# G502.net
KiCad netlist of a schematic drawn in EAGLE
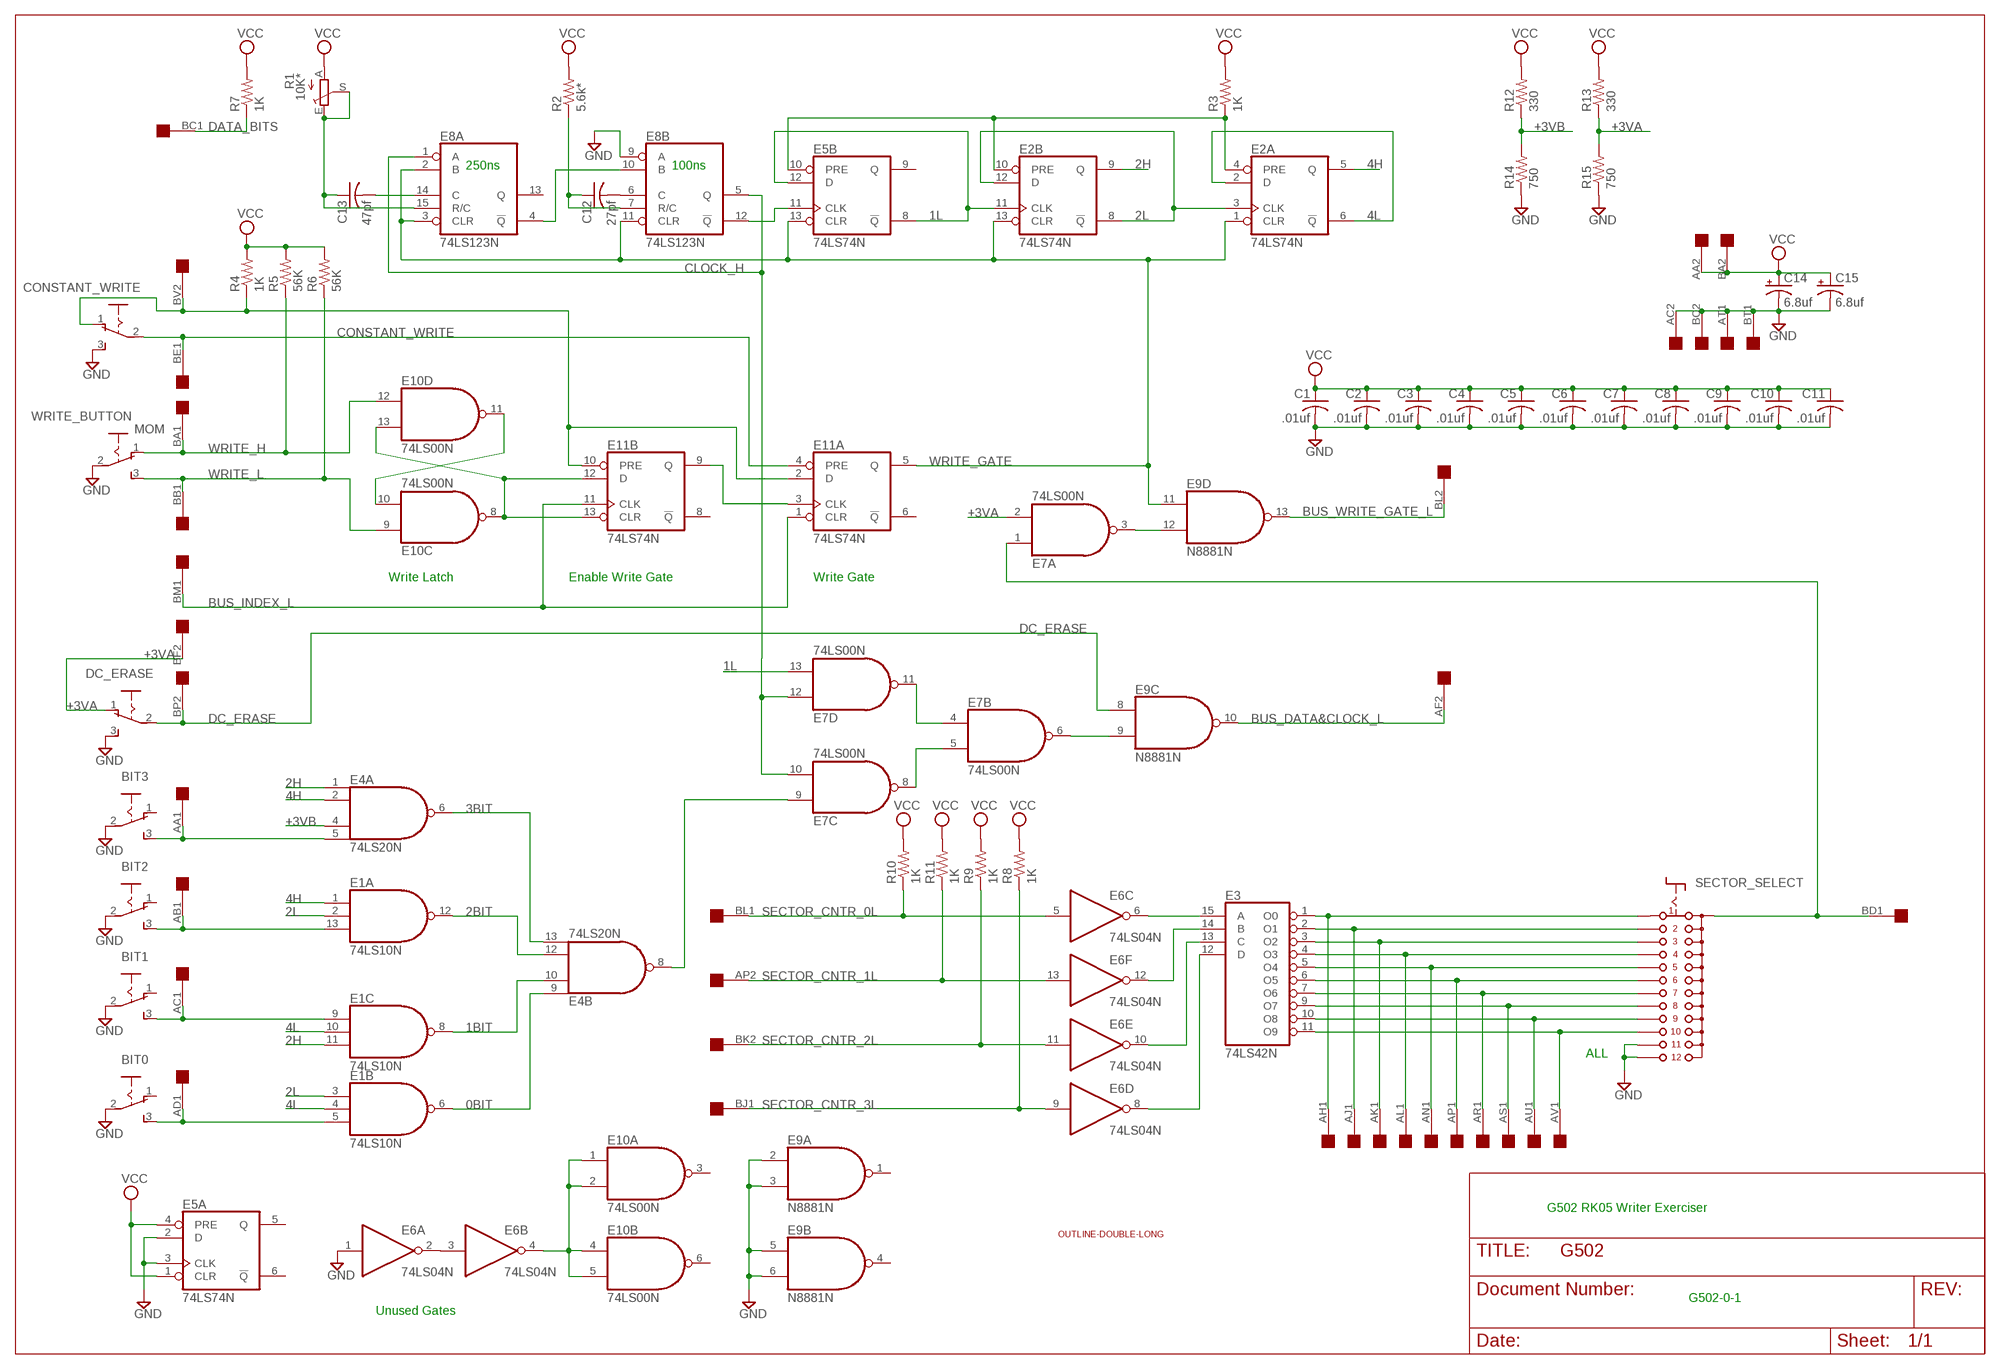
[diagram p0: schematic, sheet 1]

(export (version "E")
  (design (tool "Eeschema 10.0.6"))
  (components
    (comp (ref "AB04")
      (value "DOUBLE")
      (footprint "eagle-import:EDGE-CON4")
      (libsource (lib "eagle-import") (part "DOUBLE"))
    )
    (comp (ref "BIT0")
      (value "255SB")
      (footprint "eagle-import:255SB")
      (libsource (lib "eagle-import") (part "255SB"))
    )
    (comp (ref "BIT1")
      (value "255SB")
      (footprint "eagle-import:255SB")
      (libsource (lib "eagle-import") (part "255SB"))
    )
    (comp (ref "BIT2")
      (value "255SB")
      (footprint "eagle-import:255SB")
      (libsource (lib "eagle-import") (part "255SB"))
    )
    (comp (ref "BIT3")
      (value "255SB")
      (footprint "eagle-import:255SB")
      (libsource (lib "eagle-import") (part "255SB"))
    )
    (comp (ref "C1")
      (value ".01uf")
      (footprint "eagle-import:C075-032X103")
      (libsource (lib "eagle-import") (part "C-US075-032X103"))
    )
    (comp (ref "C2")
      (value ".01uf")
      (footprint "eagle-import:C075-032X103")
      (libsource (lib "eagle-import") (part "C-US075-032X103"))
    )
    (comp (ref "C3")
      (value ".01uf")
      (footprint "eagle-import:C075-032X103")
      (libsource (lib "eagle-import") (part "C-US075-032X103"))
    )
    (comp (ref "C4")
      (value ".01uf")
      (footprint "eagle-import:C075-032X103")
      (libsource (lib "eagle-import") (part "C-US075-032X103"))
    )
    (comp (ref "C5")
      (value ".01uf")
      (footprint "eagle-import:C075-032X103")
      (libsource (lib "eagle-import") (part "C-US075-032X103"))
    )
    (comp (ref "C6")
      (value ".01uf")
      (footprint "eagle-import:C075-032X103")
      (libsource (lib "eagle-import") (part "C-US075-032X103"))
    )
    (comp (ref "C7")
      (value ".01uf")
      (footprint "eagle-import:C075-032X103")
      (libsource (lib "eagle-import") (part "C-US075-032X103"))
    )
    (comp (ref "C8")
      (value ".01uf")
      (footprint "eagle-import:C075-032X103")
      (libsource (lib "eagle-import") (part "C-US075-032X103"))
    )
    (comp (ref "C9")
      (value ".01uf")
      (footprint "eagle-import:C075-032X103")
      (libsource (lib "eagle-import") (part "C-US075-032X103"))
    )
    (comp (ref "C10")
      (value ".01uf")
      (footprint "eagle-import:C075-032X103")
      (libsource (lib "eagle-import") (part "C-US075-032X103"))
    )
    (comp (ref "C11")
      (value ".01uf")
      (footprint "eagle-import:C075-032X103")
      (libsource (lib "eagle-import") (part "C-US075-032X103"))
    )
    (comp (ref "C12")
      (value "27pf")
      (footprint "eagle-import:C075-032X103")
      (libsource (lib "eagle-import") (part "C-US075-032X103"))
    )
    (comp (ref "C13")
      (value "47pf")
      (footprint "eagle-import:C075-032X103")
      (libsource (lib "eagle-import") (part "C-US075-032X103"))
    )
    (comp (ref "C14")
      (value "6.8uf")
      (footprint "eagle-import:E25-9")
      (libsource (lib "eagle-import") (part "CPOL-USE25-9AXIAL"))
    )
    (comp (ref "C15")
      (value "6.8uf")
      (footprint "eagle-import:E25-9")
      (libsource (lib "eagle-import") (part "CPOL-USE25-9AXIAL"))
    )
    (comp (ref "CONSTANT_WRITE")
      (value "255SB")
      (footprint "eagle-import:255SB")
      (libsource (lib "eagle-import") (part "255SB"))
    )
    (comp (ref "DC_ERASE")
      (value "255SB")
      (footprint "eagle-import:255SB")
      (libsource (lib "eagle-import") (part "255SB"))
    )
    (comp (ref "E1")
      (value "74LS10N")
      (footprint "eagle-import:DIL14")
      (libsource (lib "eagle-import") (part "7410NLS"))
    )
    (comp (ref "E2")
      (value "74LS74N")
      (footprint "eagle-import:DIL14")
      (libsource (lib "eagle-import") (part "7474NLS"))
    )
    (comp (ref "E3")
      (value "74LS42N")
      (footprint "eagle-import:DIL16")
      (libsource (lib "eagle-import") (part "7442NLS"))
    )
    (comp (ref "E4")
      (value "74LS20N")
      (footprint "eagle-import:DIL14")
      (libsource (lib "eagle-import") (part "7420NLS"))
    )
    (comp (ref "E5")
      (value "74LS74N")
      (footprint "eagle-import:DIL14")
      (libsource (lib "eagle-import") (part "7474NLS"))
    )
    (comp (ref "E6")
      (value "74LS04N")
      (footprint "eagle-import:DIL14")
      (libsource (lib "eagle-import") (part "7404NLS"))
    )
    (comp (ref "E7")
      (value "74LS00N")
      (footprint "eagle-import:DIL14")
      (libsource (lib "eagle-import") (part "7400NLS"))
    )
    (comp (ref "E8")
      (value "74LS123N")
      (footprint "eagle-import:DIL16")
      (libsource (lib "eagle-import") (part "74123NLS"))
    )
    (comp (ref "E9")
      (value "N8881N")
      (footprint "eagle-import:DIL14")
      (libsource (lib "eagle-import") (part "N8881N"))
    )
    (comp (ref "E10")
      (value "74LS00N")
      (footprint "eagle-import:DIL14")
      (libsource (lib "eagle-import") (part "7400NLS"))
    )
    (comp (ref "E11")
      (value "74LS74N")
      (footprint "eagle-import:DIL14")
      (libsource (lib "eagle-import") (part "7474NLS"))
    )
    (comp (ref "R1")
      (value "10K*")
      (footprint "eagle-import:SP19L")
      (libsource (lib "eagle-import") (part "TRIM_EU-B90P"))
    )
    (comp (ref "R2")
      (value "5.6k*")
      (footprint "eagle-import:0207_10")
      (libsource (lib "eagle-import") (part "R-US_0207/10"))
    )
    (comp (ref "R3")
      (value "1K")
      (footprint "eagle-import:0207_10")
      (libsource (lib "eagle-import") (part "R-US_0207/10"))
    )
    (comp (ref "R4")
      (value "1K")
      (footprint "eagle-import:0207_10")
      (libsource (lib "eagle-import") (part "R-US_0207/10"))
    )
    (comp (ref "R5")
      (value "56K")
      (footprint "eagle-import:0207_10")
      (libsource (lib "eagle-import") (part "R-US_0207/10"))
    )
    (comp (ref "R6")
      (value "56K")
      (footprint "eagle-import:0207_10")
      (libsource (lib "eagle-import") (part "R-US_0207/10"))
    )
    (comp (ref "R7")
      (value "1K")
      (footprint "eagle-import:0207_10")
      (libsource (lib "eagle-import") (part "R-US_0207/10"))
    )
    (comp (ref "R8")
      (value "1K")
      (footprint "eagle-import:0207_10")
      (libsource (lib "eagle-import") (part "R-US_0207/10"))
    )
    (comp (ref "R9")
      (value "1K")
      (footprint "eagle-import:0207_10")
      (libsource (lib "eagle-import") (part "R-US_0207/10"))
    )
    (comp (ref "R10")
      (value "1K")
      (footprint "eagle-import:0207_10")
      (libsource (lib "eagle-import") (part "R-US_0207/10"))
    )
    (comp (ref "R11")
      (value "1K")
      (footprint "eagle-import:0207_10")
      (libsource (lib "eagle-import") (part "R-US_0207/10"))
    )
    (comp (ref "R12")
      (value "330")
      (footprint "eagle-import:0207_10")
      (libsource (lib "eagle-import") (part "R-US_0207/10"))
    )
    (comp (ref "R13")
      (value "330")
      (footprint "eagle-import:0207_10")
      (libsource (lib "eagle-import") (part "R-US_0207/10"))
    )
    (comp (ref "R14")
      (value "750")
      (footprint "eagle-import:0207_10")
      (libsource (lib "eagle-import") (part "R-US_0207/10"))
    )
    (comp (ref "R15")
      (value "750")
      (footprint "eagle-import:0207_10")
      (libsource (lib "eagle-import") (part "R-US_0207/10"))
    )
    (comp (ref "SECTOR_SELECT")
      (value "CK101X12")
      (footprint "eagle-import:CK101X12")
      (libsource (lib "eagle-import") (part "CK101X12"))
    )
    (comp (ref "U$2")
      (value "OUTLINE-DOUBLE-LONG")
      (footprint "eagle-import:DOUBLE-LONG")
      (libsource (lib "eagle-import") (part "OUTLINE-DOUBLE-LONG"))
    )
    (comp (ref "WRITE_BUTTON")
      (value "MOM")
      (footprint "eagle-import:255SB")
      (libsource (lib "eagle-import") (part "255SB"))
    )
  )
  (nets
    (net (code "1") (name "/+3VA") (class "Default")
      (node (ref "AB04") (pin "BF2") (pinfunction "1_BF2") (pintype "bidirectional"))
      (node (ref "DC_ERASE") (pin "1") (pinfunction "O_1") (pintype "passive"))
      (node (ref "E7") (pin "2") (pinfunction "I1_2") (pintype "input"))
      (node (ref "R13") (pin "1") (pinfunction "1_1") (pintype "passive"))
      (node (ref "R15") (pin "2") (pinfunction "2_2") (pintype "passive"))
    )
    (net (code "2") (name "/+3VB") (class "Default")
      (node (ref "E4") (pin "4") (pinfunction "I2_4") (pintype "input"))
      (node (ref "R12") (pin "1") (pinfunction "1_1") (pintype "passive"))
      (node (ref "R14") (pin "2") (pinfunction "2_2") (pintype "passive"))
    )
    (net (code "3") (name "/0BIT") (class "Default")
      (node (ref "E1") (pin "6") (pinfunction "O_6") (pintype "output"))
      (node (ref "E4") (pin "9") (pinfunction "I0_9") (pintype "input"))
    )
    (net (code "4") (name "/1BIT") (class "Default")
      (node (ref "E1") (pin "8") (pinfunction "O_8") (pintype "output"))
      (node (ref "E4") (pin "10") (pinfunction "I1_10") (pintype "input"))
    )
    (net (code "5") (name "/1L") (class "Default")
      (node (ref "E2") (pin "11") (pinfunction "CLK_11") (pintype "input"))
      (node (ref "E5") (pin "12") (pinfunction "D_12") (pintype "input"))
      (node (ref "E5") (pin "8") (pinfunction "~{Q}_8") (pintype "output"))
      (node (ref "E7") (pin "13") (pinfunction "I1_13") (pintype "input"))
    )
    (net (code "6") (name "/2BIT") (class "Default")
      (node (ref "E1") (pin "12") (pinfunction "O_12") (pintype "output"))
      (node (ref "E4") (pin "12") (pinfunction "I2_12") (pintype "input"))
    )
    (net (code "7") (name "/2H") (class "Default")
      (node (ref "E1") (pin "11") (pinfunction "I2_11") (pintype "input"))
      (node (ref "E2") (pin "9") (pinfunction "Q_9") (pintype "output"))
      (node (ref "E4") (pin "1") (pinfunction "I0_1") (pintype "input"))
    )
    (net (code "8") (name "/2L") (class "Default")
      (node (ref "E1") (pin "2") (pinfunction "I1_2") (pintype "input"))
      (node (ref "E1") (pin "3") (pinfunction "I0_3") (pintype "input"))
      (node (ref "E2") (pin "12") (pinfunction "D_12") (pintype "input"))
      (node (ref "E2") (pin "3") (pinfunction "CLK_3") (pintype "input"))
      (node (ref "E2") (pin "8") (pinfunction "~{Q}_8") (pintype "output"))
    )
    (net (code "9") (name "/3BIT") (class "Default")
      (node (ref "E4") (pin "13") (pinfunction "I3_13") (pintype "input"))
      (node (ref "E4") (pin "6") (pinfunction "O_6") (pintype "output"))
    )
    (net (code "10") (name "/4H") (class "Default")
      (node (ref "E1") (pin "1") (pinfunction "I0_1") (pintype "input"))
      (node (ref "E2") (pin "5") (pinfunction "Q_5") (pintype "output"))
      (node (ref "E4") (pin "2") (pinfunction "I1_2") (pintype "input"))
    )
    (net (code "11") (name "/4L") (class "Default")
      (node (ref "E1") (pin "10") (pinfunction "I1_10") (pintype "input"))
      (node (ref "E1") (pin "4") (pinfunction "I1_4") (pintype "input"))
      (node (ref "E2") (pin "2") (pinfunction "D_2") (pintype "input"))
      (node (ref "E2") (pin "6") (pinfunction "~{Q}_6") (pintype "output"))
    )
    (net (code "12") (name "/BUS_DATA&CLOCK_L") (class "Default")
      (node (ref "AB04") (pin "AF2") (pinfunction "1_AF2") (pintype "bidirectional"))
      (node (ref "E9") (pin "10") (pinfunction "O_10") (pintype "open_collector"))
    )
    (net (code "13") (name "/BUS_INDEX_L") (class "Default")
      (node (ref "AB04") (pin "BM1") (pinfunction "1_BM1") (pintype "bidirectional"))
      (node (ref "E11") (pin "1") (pinfunction "CLR_1") (pintype "input"))
      (node (ref "E11") (pin "11") (pinfunction "CLK_11") (pintype "input"))
    )
    (net (code "14") (name "/BUS_WRITE_GATE_L") (class "Default")
      (node (ref "AB04") (pin "BL2") (pinfunction "1_BL2") (pintype "bidirectional"))
      (node (ref "E9") (pin "13") (pinfunction "O_13") (pintype "open_collector"))
    )
    (net (code "15") (name "/CLOCK_H") (class "Default")
      (node (ref "E7") (pin "10") (pinfunction "I1_10") (pintype "input"))
      (node (ref "E7") (pin "12") (pinfunction "I0_12") (pintype "input"))
      (node (ref "E8") (pin "1") (pinfunction "A_1") (pintype "input"))
      (node (ref "E8") (pin "5") (pinfunction "Q_5") (pintype "output"))
    )
    (net (code "16") (name "/CONSTANT_WRITE") (class "Default")
      (node (ref "AB04") (pin "BE1") (pinfunction "1_BE1") (pintype "bidirectional"))
      (node (ref "CONSTANT_WRITE") (pin "2") (pinfunction "P_2") (pintype "passive"))
      (node (ref "E11") (pin "4") (pinfunction "PRE_4") (pintype "input"))
    )
    (net (code "17") (name "/DATA_BITS") (class "Default")
      (node (ref "AB04") (pin "BC1") (pinfunction "1_BC1") (pintype "bidirectional"))
      (node (ref "R7") (pin "1") (pinfunction "1_1") (pintype "passive"))
    )
    (net (code "18") (name "/DC_ERASE") (class "Default")
      (node (ref "AB04") (pin "BP2") (pinfunction "1_BP2") (pintype "bidirectional"))
      (node (ref "DC_ERASE") (pin "2") (pinfunction "P_2") (pintype "passive"))
      (node (ref "E9") (pin "8") (pinfunction "I0_8") (pintype "input"))
    )
    (net (code "19") (name "/SECTOR_CNTR_0L") (class "Default")
      (node (ref "AB04") (pin "BL1") (pinfunction "1_BL1") (pintype "bidirectional"))
      (node (ref "E6") (pin "5") (pinfunction "I_5") (pintype "input"))
      (node (ref "R10") (pin "1") (pinfunction "1_1") (pintype "passive"))
    )
    (net (code "20") (name "/SECTOR_CNTR_1L") (class "Default")
      (node (ref "AB04") (pin "AP2") (pinfunction "1_AP2") (pintype "bidirectional"))
      (node (ref "E6") (pin "13") (pinfunction "I_13") (pintype "input"))
      (node (ref "R11") (pin "1") (pinfunction "1_1") (pintype "passive"))
    )
    (net (code "21") (name "/SECTOR_CNTR_2L") (class "Default")
      (node (ref "AB04") (pin "BK2") (pinfunction "1_BK2") (pintype "bidirectional"))
      (node (ref "E6") (pin "11") (pinfunction "I_11") (pintype "input"))
      (node (ref "R9") (pin "1") (pinfunction "1_1") (pintype "passive"))
    )
    (net (code "22") (name "/SECTOR_CNTR_3L") (class "Default")
      (node (ref "AB04") (pin "BJ1") (pinfunction "1_BJ1") (pintype "bidirectional"))
      (node (ref "E6") (pin "9") (pinfunction "I_9") (pintype "input"))
      (node (ref "R8") (pin "1") (pinfunction "1_1") (pintype "passive"))
    )
    (net (code "23") (name "/WRITE_GATE") (class "Default")
      (node (ref "E11") (pin "5") (pinfunction "Q_5") (pintype "output"))
      (node (ref "E2") (pin "1") (pinfunction "CLR_1") (pintype "input"))
      (node (ref "E2") (pin "13") (pinfunction "CLR_13") (pintype "input"))
      (node (ref "E5") (pin "13") (pinfunction "CLR_13") (pintype "input"))
      (node (ref "E8") (pin "11") (pinfunction "CLR_11") (pintype "input"))
      (node (ref "E8") (pin "2") (pinfunction "B_2") (pintype "input"))
      (node (ref "E8") (pin "3") (pinfunction "CLR_3") (pintype "input"))
      (node (ref "E9") (pin "11") (pinfunction "I0_11") (pintype "input"))
    )
    (net (code "24") (name "/WRITE_H") (class "Default")
      (node (ref "AB04") (pin "BA1") (pinfunction "1_BA1") (pintype "bidirectional"))
      (node (ref "E10") (pin "12") (pinfunction "I0_12") (pintype "input"))
      (node (ref "R5") (pin "1") (pinfunction "1_1") (pintype "passive"))
      (node (ref "WRITE_BUTTON") (pin "1") (pinfunction "O_1") (pintype "passive"))
    )
    (net (code "25") (name "/WRITE_L") (class "Default")
      (node (ref "AB04") (pin "BB1") (pinfunction "1_BB1") (pintype "bidirectional"))
      (node (ref "E10") (pin "9") (pinfunction "I0_9") (pintype "input"))
      (node (ref "R6") (pin "1") (pinfunction "1_1") (pintype "passive"))
      (node (ref "WRITE_BUTTON") (pin "3") (pinfunction "S_3") (pintype "passive"))
    )
    (net (code "26") (name "GND") (class "Default")
      (node (ref "AB04") (pin "AC2") (pinfunction "1_AC2") (pintype "bidirectional"))
      (node (ref "AB04") (pin "AT1") (pinfunction "1_AT1") (pintype "bidirectional"))
      (node (ref "AB04") (pin "BC2") (pinfunction "1_BC2") (pintype "bidirectional"))
      (node (ref "AB04") (pin "BT1") (pinfunction "1_BT1") (pintype "bidirectional"))
      (node (ref "BIT0") (pin "2") (pinfunction "P_2") (pintype "passive"))
      (node (ref "BIT1") (pin "2") (pinfunction "P_2") (pintype "passive"))
      (node (ref "BIT2") (pin "2") (pinfunction "P_2") (pintype "passive"))
      (node (ref "BIT3") (pin "2") (pinfunction "P_2") (pintype "passive"))
      (node (ref "C1") (pin "2") (pinfunction "2_2") (pintype "passive"))
      (node (ref "C10") (pin "2") (pinfunction "2_2") (pintype "passive"))
      (node (ref "C11") (pin "2") (pinfunction "2_2") (pintype "passive"))
      (node (ref "C14") (pin "-") (pinfunction "-_-") (pintype "passive"))
      (node (ref "C15") (pin "-") (pinfunction "-_-") (pintype "passive"))
      (node (ref "C2") (pin "2") (pinfunction "2_2") (pintype "passive"))
      (node (ref "C3") (pin "2") (pinfunction "2_2") (pintype "passive"))
      (node (ref "C4") (pin "2") (pinfunction "2_2") (pintype "passive"))
      (node (ref "C5") (pin "2") (pinfunction "2_2") (pintype "passive"))
      (node (ref "C6") (pin "2") (pinfunction "2_2") (pintype "passive"))
      (node (ref "C7") (pin "2") (pinfunction "2_2") (pintype "passive"))
      (node (ref "C8") (pin "2") (pinfunction "2_2") (pintype "passive"))
      (node (ref "C9") (pin "2") (pinfunction "2_2") (pintype "passive"))
      (node (ref "CONSTANT_WRITE") (pin "3") (pinfunction "S_3") (pintype "passive"))
      (node (ref "DC_ERASE") (pin "3") (pinfunction "S_3") (pintype "passive"))
      (node (ref "E5") (pin "2") (pinfunction "D_2") (pintype "input"))
      (node (ref "E5") (pin "3") (pinfunction "CLK_3") (pintype "input"))
      (node (ref "E6") (pin "1") (pinfunction "I_1") (pintype "input"))
      (node (ref "E8") (pin "9") (pinfunction "A_9") (pintype "input"))
      (node (ref "E9") (pin "2") (pinfunction "I0_2") (pintype "input"))
      (node (ref "E9") (pin "3") (pinfunction "I1_3") (pintype "input"))
      (node (ref "E9") (pin "5") (pinfunction "I0_5") (pintype "input"))
      (node (ref "E9") (pin "6") (pinfunction "I1_6") (pintype "input"))
      (node (ref "R14") (pin "1") (pinfunction "1_1") (pintype "passive"))
      (node (ref "R15") (pin "1") (pinfunction "1_1") (pintype "passive"))
      (node (ref "SECTOR_SELECT") (pin "11") (pinfunction "11_11") (pintype "passive"))
      (node (ref "SECTOR_SELECT") (pin "12") (pinfunction "12_12") (pintype "passive"))
      (node (ref "WRITE_BUTTON") (pin "2") (pinfunction "P_2") (pintype "passive"))
    )
    (net (code "27") (name "Net-(AB04A-1)") (class "Default")
      (node (ref "AB04") (pin "AA1") (pinfunction "1_AA1") (pintype "bidirectional"))
      (node (ref "BIT3") (pin "3") (pinfunction "S_3") (pintype "passive"))
      (node (ref "E4") (pin "5") (pinfunction "I3_5") (pintype "input"))
    )
    (net (code "28") (name "Net-(AB04AA-1)") (class "Default")
      (node (ref "AB04") (pin "AR1") (pinfunction "1_AR1") (pintype "bidirectional"))
      (node (ref "E3") (pin "7") (pinfunction "O6_7") (pintype "output"))
      (node (ref "SECTOR_SELECT") (pin "7") (pinfunction "7_7") (pintype "passive"))
    )
    (net (code "29") (name "Net-(AB04AC-1)") (class "Default")
      (node (ref "AB04") (pin "AS1") (pinfunction "1_AS1") (pintype "bidirectional"))
      (node (ref "E3") (pin "9") (pinfunction "O7_9") (pintype "output"))
      (node (ref "SECTOR_SELECT") (pin "8") (pinfunction "8_8") (pintype "passive"))
    )
    (net (code "30") (name "Net-(AB04AG-1)") (class "Default")
      (node (ref "AB04") (pin "AU1") (pinfunction "1_AU1") (pintype "bidirectional"))
      (node (ref "E3") (pin "10") (pinfunction "O8_10") (pintype "output"))
      (node (ref "SECTOR_SELECT") (pin "9") (pinfunction "9_9") (pintype "passive"))
    )
    (net (code "31") (name "Net-(AB04AI-1)") (class "Default")
      (node (ref "AB04") (pin "AV1") (pinfunction "1_AV1") (pintype "bidirectional"))
      (node (ref "E3") (pin "11") (pinfunction "O9_11") (pintype "output"))
      (node (ref "SECTOR_SELECT") (pin "10") (pinfunction "10_10") (pintype "passive"))
    )
    (net (code "32") (name "Net-(AB04AQ-1)") (class "Default")
      (node (ref "AB04") (pin "BD1") (pinfunction "1_BD1") (pintype "bidirectional"))
      (node (ref "E7") (pin "1") (pinfunction "I0_1") (pintype "input"))
      (node (ref "SECTOR_SELECT") (pin "A") (pinfunction "A_A") (pintype "passive"))
    )
    (net (code "33") (name "Net-(AB04BT-1)") (class "Default")
      (node (ref "AB04") (pin "BV2") (pinfunction "1_BV2") (pintype "bidirectional"))
      (node (ref "CONSTANT_WRITE") (pin "1") (pinfunction "O_1") (pintype "passive"))
      (node (ref "E11") (pin "10") (pinfunction "PRE_10") (pintype "input"))
      (node (ref "E11") (pin "2") (pinfunction "D_2") (pintype "input"))
      (node (ref "R4") (pin "1") (pinfunction "1_1") (pintype "passive"))
    )
    (net (code "34") (name "Net-(AB04C-1)") (class "Default")
      (node (ref "AB04") (pin "AB1") (pinfunction "1_AB1") (pintype "bidirectional"))
      (node (ref "BIT2") (pin "3") (pinfunction "S_3") (pintype "passive"))
      (node (ref "E1") (pin "13") (pinfunction "I2_13") (pintype "input"))
    )
    (net (code "35") (name "Net-(AB04E-1)") (class "Default")
      (node (ref "AB04") (pin "AC1") (pinfunction "1_AC1") (pintype "bidirectional"))
      (node (ref "BIT1") (pin "3") (pinfunction "S_3") (pintype "passive"))
      (node (ref "E1") (pin "9") (pinfunction "I0_9") (pintype "input"))
    )
    (net (code "36") (name "Net-(AB04G-1)") (class "Default")
      (node (ref "AB04") (pin "AD1") (pinfunction "1_AD1") (pintype "bidirectional"))
      (node (ref "BIT0") (pin "3") (pinfunction "S_3") (pintype "passive"))
      (node (ref "E1") (pin "5") (pinfunction "I2_5") (pintype "input"))
    )
    (net (code "37") (name "Net-(AB04M-1)") (class "Default")
      (node (ref "AB04") (pin "AH1") (pinfunction "1_AH1") (pintype "bidirectional"))
      (node (ref "E3") (pin "1") (pinfunction "O0_1") (pintype "output"))
      (node (ref "SECTOR_SELECT") (pin "1") (pinfunction "1_1") (pintype "passive"))
    )
    (net (code "38") (name "Net-(AB04O-1)") (class "Default")
      (node (ref "AB04") (pin "AJ1") (pinfunction "1_AJ1") (pintype "bidirectional"))
      (node (ref "E3") (pin "2") (pinfunction "O1_2") (pintype "output"))
      (node (ref "SECTOR_SELECT") (pin "2") (pinfunction "2_2") (pintype "passive"))
    )
    (net (code "39") (name "Net-(AB04Q-1)") (class "Default")
      (node (ref "AB04") (pin "AK1") (pinfunction "1_AK1") (pintype "bidirectional"))
      (node (ref "E3") (pin "3") (pinfunction "O2_3") (pintype "output"))
      (node (ref "SECTOR_SELECT") (pin "3") (pinfunction "3_3") (pintype "passive"))
    )
    (net (code "40") (name "Net-(AB04S-1)") (class "Default")
      (node (ref "AB04") (pin "AL1") (pinfunction "1_AL1") (pintype "bidirectional"))
      (node (ref "E3") (pin "4") (pinfunction "O3_4") (pintype "output"))
      (node (ref "SECTOR_SELECT") (pin "4") (pinfunction "4_4") (pintype "passive"))
    )
    (net (code "41") (name "Net-(AB04W-1)") (class "Default")
      (node (ref "AB04") (pin "AN1") (pinfunction "1_AN1") (pintype "bidirectional"))
      (node (ref "E3") (pin "5") (pinfunction "O4_5") (pintype "output"))
      (node (ref "SECTOR_SELECT") (pin "5") (pinfunction "5_5") (pintype "passive"))
    )
    (net (code "42") (name "Net-(AB04Y-1)") (class "Default")
      (node (ref "AB04") (pin "AP1") (pinfunction "1_AP1") (pintype "bidirectional"))
      (node (ref "E3") (pin "6") (pinfunction "O5_6") (pintype "output"))
      (node (ref "SECTOR_SELECT") (pin "6") (pinfunction "6_6") (pintype "passive"))
    )
    (net (code "43") (name "Net-(E2A-PRE)") (class "Default")
      (node (ref "E2") (pin "10") (pinfunction "PRE_10") (pintype "input"))
      (node (ref "E2") (pin "4") (pinfunction "PRE_4") (pintype "input"))
      (node (ref "E5") (pin "10") (pinfunction "PRE_10") (pintype "input"))
      (node (ref "R3") (pin "1") (pinfunction "1_1") (pintype "passive"))
    )
    (net (code "44") (name "Net-(E3A-A)") (class "Default")
      (node (ref "E3") (pin "15") (pinfunction "A_15") (pintype "input"))
      (node (ref "E6") (pin "6") (pinfunction "O_6") (pintype "output"))
    )
    (net (code "45") (name "Net-(E3A-B)") (class "Default")
      (node (ref "E3") (pin "14") (pinfunction "B_14") (pintype "input"))
      (node (ref "E6") (pin "12") (pinfunction "O_12") (pintype "output"))
    )
    (net (code "46") (name "Net-(E3A-C)") (class "Default")
      (node (ref "E3") (pin "13") (pinfunction "C_13") (pintype "input"))
      (node (ref "E6") (pin "10") (pinfunction "O_10") (pintype "output"))
    )
    (net (code "47") (name "Net-(E3A-D)") (class "Default")
      (node (ref "E3") (pin "12") (pinfunction "D_12") (pintype "input"))
      (node (ref "E6") (pin "8") (pinfunction "O_8") (pintype "output"))
    )
    (net (code "48") (name "Net-(E4B-O)") (class "Default")
      (node (ref "E4") (pin "8") (pinfunction "O_8") (pintype "output"))
      (node (ref "E7") (pin "9") (pinfunction "I0_9") (pintype "input"))
    )
    (net (code "49") (name "Net-(E5B-CLK)") (class "Default")
      (node (ref "E5") (pin "11") (pinfunction "CLK_11") (pintype "input"))
      (node (ref "E8") (pin "12") (pinfunction "~{Q}_12") (pintype "output"))
    )
    (net (code "50") (name "Net-(E6A-O)") (class "Default")
      (node (ref "E6") (pin "2") (pinfunction "O_2") (pintype "output"))
      (node (ref "E6") (pin "3") (pinfunction "I_3") (pintype "input"))
    )
    (net (code "51") (name "Net-(E7A-O)") (class "Default")
      (node (ref "E7") (pin "3") (pinfunction "O_3") (pintype "output"))
      (node (ref "E9") (pin "12") (pinfunction "I1_12") (pintype "input"))
    )
    (net (code "52") (name "Net-(E7B-I0)") (class "Default")
      (node (ref "E7") (pin "11") (pinfunction "O_11") (pintype "output"))
      (node (ref "E7") (pin "4") (pinfunction "I0_4") (pintype "input"))
    )
    (net (code "53") (name "Net-(E7B-I1)") (class "Default")
      (node (ref "E7") (pin "5") (pinfunction "I1_5") (pintype "input"))
      (node (ref "E7") (pin "8") (pinfunction "O_8") (pintype "output"))
    )
    (net (code "54") (name "Net-(E7B-O)") (class "Default")
      (node (ref "E7") (pin "6") (pinfunction "O_6") (pintype "output"))
      (node (ref "E9") (pin "9") (pinfunction "I1_9") (pintype "input"))
    )
    (net (code "55") (name "Net-(E8A-C)") (class "Default")
      (node (ref "C13") (pin "2") (pinfunction "2_2") (pintype "passive"))
      (node (ref "E8") (pin "14") (pinfunction "C_14") (pintype "input"))
    )
    (net (code "56") (name "Net-(E8A-R{slash}C)") (class "Default")
      (node (ref "C13") (pin "1") (pinfunction "1_1") (pintype "passive"))
      (node (ref "E8") (pin "15") (pinfunction "R/C_15") (pintype "input"))
      (node (ref "R1") (pin "E") (pinfunction "E_E") (pintype "passive"))
      (node (ref "R1") (pin "S") (pinfunction "S_S") (pintype "passive"))
    )
    (net (code "57") (name "Net-(E8A-~{Q})") (class "Default")
      (node (ref "E8") (pin "10") (pinfunction "B_10") (pintype "input"))
      (node (ref "E8") (pin "4") (pinfunction "~{Q}_4") (pintype "output"))
    )
    (net (code "58") (name "Net-(E8B-C)") (class "Default")
      (node (ref "C12") (pin "2") (pinfunction "2_2") (pintype "passive"))
      (node (ref "E8") (pin "6") (pinfunction "C_6") (pintype "input"))
    )
    (net (code "59") (name "Net-(E8B-R{slash}C)") (class "Default")
      (node (ref "C12") (pin "1") (pinfunction "1_1") (pintype "passive"))
      (node (ref "E8") (pin "7") (pinfunction "R/C_7") (pintype "input"))
      (node (ref "R2") (pin "1") (pinfunction "1_1") (pintype "passive"))
    )
    (net (code "60") (name "Net-(E10A-I0)") (class "Default")
      (node (ref "E10") (pin "1") (pinfunction "I0_1") (pintype "input"))
      (node (ref "E10") (pin "2") (pinfunction "I1_2") (pintype "input"))
      (node (ref "E10") (pin "4") (pinfunction "I0_4") (pintype "input"))
      (node (ref "E10") (pin "5") (pinfunction "I1_5") (pintype "input"))
      (node (ref "E6") (pin "4") (pinfunction "O_4") (pintype "output"))
    )
    (net (code "61") (name "Net-(E10C-I1)") (class "Default")
      (node (ref "E10") (pin "10") (pinfunction "I1_10") (pintype "input"))
      (node (ref "E10") (pin "11") (pinfunction "O_11") (pintype "output"))
    )
    (net (code "62") (name "Net-(E10C-O)") (class "Default")
      (node (ref "E10") (pin "13") (pinfunction "I1_13") (pintype "input"))
      (node (ref "E10") (pin "8") (pinfunction "O_8") (pintype "output"))
      (node (ref "E11") (pin "12") (pinfunction "D_12") (pintype "input"))
      (node (ref "E11") (pin "13") (pinfunction "CLR_13") (pintype "input"))
    )
    (net (code "63") (name "Net-(E11A-CLK)") (class "Default")
      (node (ref "E11") (pin "3") (pinfunction "CLK_3") (pintype "input"))
      (node (ref "E11") (pin "9") (pinfunction "Q_9") (pintype "output"))
    )
    (net (code "64") (name "VCC") (class "Default")
      (node (ref "AB04") (pin "AA2") (pinfunction "1_AA2") (pintype "bidirectional"))
      (node (ref "AB04") (pin "BA2") (pinfunction "1_BA2") (pintype "bidirectional"))
      (node (ref "C1") (pin "1") (pinfunction "1_1") (pintype "passive"))
      (node (ref "C10") (pin "1") (pinfunction "1_1") (pintype "passive"))
      (node (ref "C11") (pin "1") (pinfunction "1_1") (pintype "passive"))
      (node (ref "C14") (pin "+") (pinfunction "+_+") (pintype "passive"))
      (node (ref "C15") (pin "+") (pinfunction "+_+") (pintype "passive"))
      (node (ref "C2") (pin "1") (pinfunction "1_1") (pintype "passive"))
      (node (ref "C3") (pin "1") (pinfunction "1_1") (pintype "passive"))
      (node (ref "C4") (pin "1") (pinfunction "1_1") (pintype "passive"))
      (node (ref "C5") (pin "1") (pinfunction "1_1") (pintype "passive"))
      (node (ref "C6") (pin "1") (pinfunction "1_1") (pintype "passive"))
      (node (ref "C7") (pin "1") (pinfunction "1_1") (pintype "passive"))
      (node (ref "C8") (pin "1") (pinfunction "1_1") (pintype "passive"))
      (node (ref "C9") (pin "1") (pinfunction "1_1") (pintype "passive"))
      (node (ref "E5") (pin "1") (pinfunction "CLR_1") (pintype "input"))
      (node (ref "E5") (pin "4") (pinfunction "PRE_4") (pintype "input"))
      (node (ref "R1") (pin "A") (pinfunction "A_A") (pintype "passive"))
      (node (ref "R10") (pin "2") (pinfunction "2_2") (pintype "passive"))
      (node (ref "R11") (pin "2") (pinfunction "2_2") (pintype "passive"))
      (node (ref "R12") (pin "2") (pinfunction "2_2") (pintype "passive"))
      (node (ref "R13") (pin "2") (pinfunction "2_2") (pintype "passive"))
      (node (ref "R2") (pin "2") (pinfunction "2_2") (pintype "passive"))
      (node (ref "R3") (pin "2") (pinfunction "2_2") (pintype "passive"))
      (node (ref "R4") (pin "2") (pinfunction "2_2") (pintype "passive"))
      (node (ref "R5") (pin "2") (pinfunction "2_2") (pintype "passive"))
      (node (ref "R6") (pin "2") (pinfunction "2_2") (pintype "passive"))
      (node (ref "R7") (pin "2") (pinfunction "2_2") (pintype "passive"))
      (node (ref "R8") (pin "2") (pinfunction "2_2") (pintype "passive"))
      (node (ref "R9") (pin "2") (pinfunction "2_2") (pintype "passive"))
    )
    (net (code "65") (name "unconnected-(BIT0-O-Pad1)") (class "Default")
      (node (ref "BIT0") (pin "1") (pinfunction "O_1") (pintype "passive"))
    )
    (net (code "66") (name "unconnected-(BIT1-O-Pad1)") (class "Default")
      (node (ref "BIT1") (pin "1") (pinfunction "O_1") (pintype "passive"))
    )
    (net (code "67") (name "unconnected-(BIT2-O-Pad1)") (class "Default")
      (node (ref "BIT2") (pin "1") (pinfunction "O_1") (pintype "passive"))
    )
    (net (code "68") (name "unconnected-(BIT3-O-Pad1)") (class "Default")
      (node (ref "BIT3") (pin "1") (pinfunction "O_1") (pintype "passive"))
    )
    (net (code "69") (name "unconnected-(E5A-Q-Pad5)") (class "Default")
      (node (ref "E5") (pin "5") (pinfunction "Q_5") (pintype "output"))
    )
    (net (code "70") (name "unconnected-(E5A-~{Q}-Pad6)") (class "Default")
      (node (ref "E5") (pin "6") (pinfunction "~{Q}_6") (pintype "output"))
    )
    (net (code "71") (name "unconnected-(E5B-Q-Pad9)") (class "Default")
      (node (ref "E5") (pin "9") (pinfunction "Q_9") (pintype "output"))
    )
    (net (code "72") (name "unconnected-(E8A-Q-Pad13)") (class "Default")
      (node (ref "E8") (pin "13") (pinfunction "Q_13") (pintype "output"))
    )
    (net (code "73") (name "unconnected-(E9A-O-Pad1)") (class "Default")
      (node (ref "E9") (pin "1") (pinfunction "O_1") (pintype "open_collector"))
    )
    (net (code "74") (name "unconnected-(E9B-O-Pad4)") (class "Default")
      (node (ref "E9") (pin "4") (pinfunction "O_4") (pintype "open_collector"))
    )
    (net (code "75") (name "unconnected-(E10A-O-Pad3)") (class "Default")
      (node (ref "E10") (pin "3") (pinfunction "O_3") (pintype "output"))
    )
    (net (code "76") (name "unconnected-(E10B-O-Pad6)") (class "Default")
      (node (ref "E10") (pin "6") (pinfunction "O_6") (pintype "output"))
    )
    (net (code "77") (name "unconnected-(E11A-~{Q}-Pad6)") (class "Default")
      (node (ref "E11") (pin "6") (pinfunction "~{Q}_6") (pintype "output"))
    )
    (net (code "78") (name "unconnected-(E11B-~{Q}-Pad8)") (class "Default")
      (node (ref "E11") (pin "8") (pinfunction "~{Q}_8") (pintype "output"))
    )
  )
)
